# 2018.net
KiCad netlist of a schematic drawn in Altium Designer
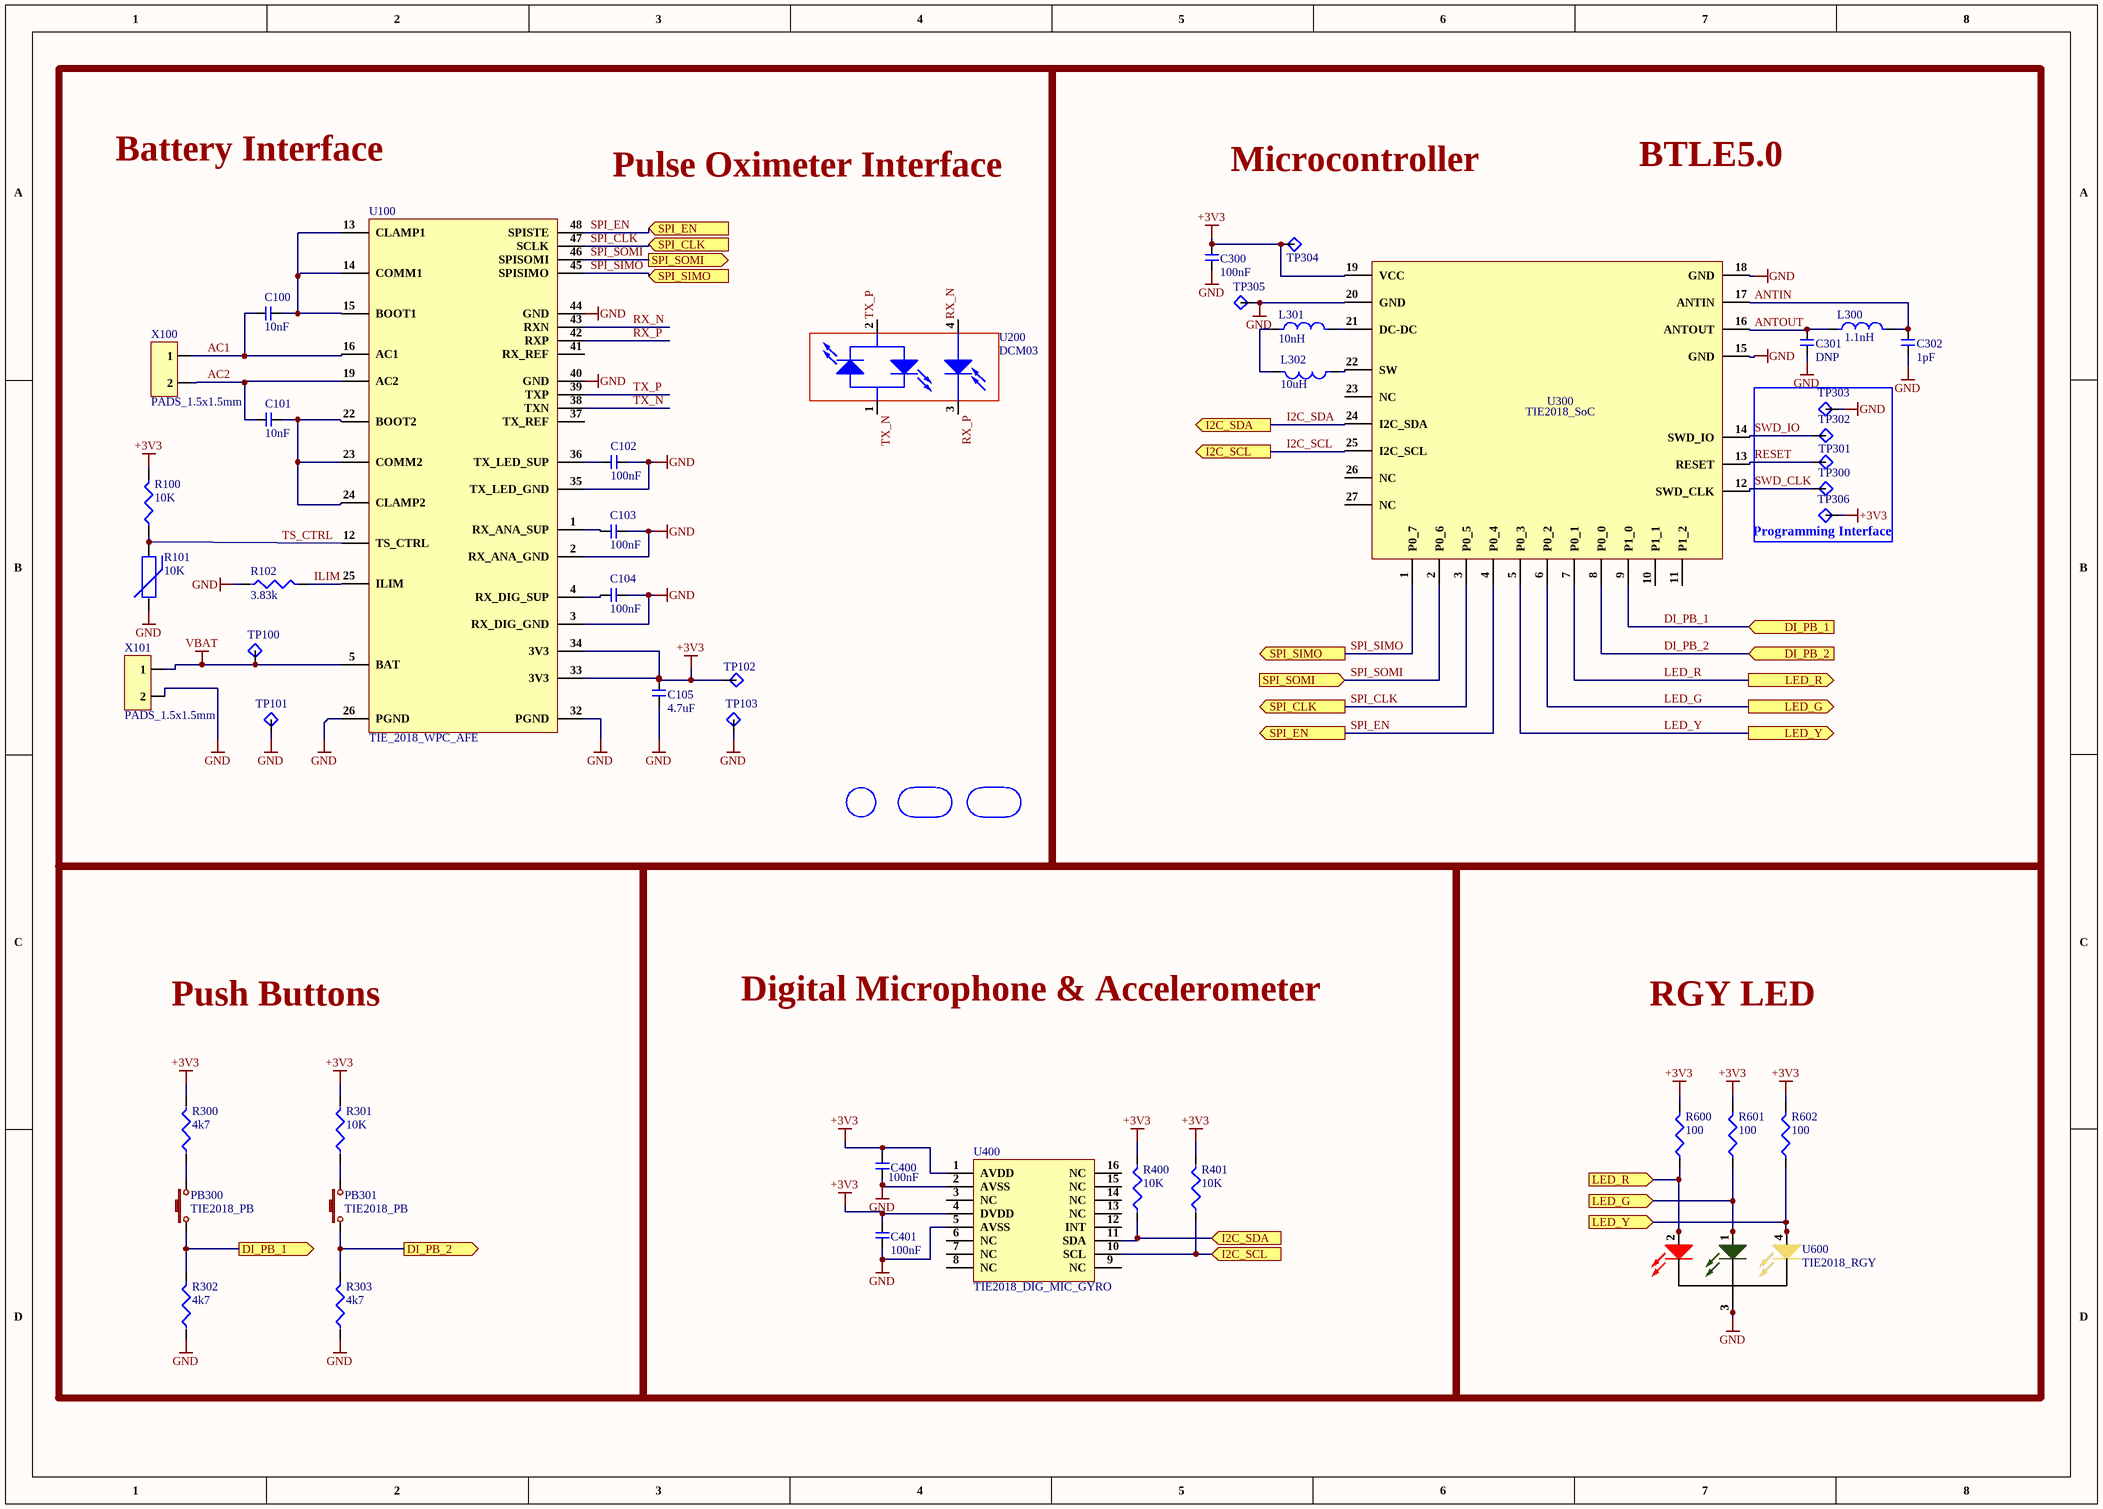
[diagram p0: 2018.SchDoc]

(export (version "E")
  (design (tool "Eeschema 10.0.6"))
  (components
    (comp (ref "C100")
      (value "10nF")
      (footprint "C0603")
      (description "Cap, 0.01ΜF, 25V, 1%, C0G/NP0, 0603")
      (fields
        (field (name "MANUFACTURER") "KEMET")
        (field (name "MANUFACTURER PART NUMBER") "C0603X103F3GACTU")
      )
      (libsource (lib "Gheorghe") (part "C0603X103F3GACTU"))
    )
    (comp (ref "C101")
      (value "10nF")
      (footprint "C0603")
      (description "Cap, 0.01ΜF, 25V, 1%, C0G/NP0, 0603")
      (fields
        (field (name "MANUFACTURER") "KEMET")
        (field (name "MANUFACTURER PART NUMBER") "C0603X103F3GACTU")
      )
      (libsource (lib "Gheorghe") (part "C0603X103F3GACTU"))
    )
    (comp (ref "C102")
      (value "100nF")
      (footprint "C0402")
      (description "Silicon Capacitor 100nF 11VDC 0402")
      (fields
        (field (name "MANUFACTURER") "Murata")
        (field (name "MANUFACTURER PART NUMBER") "939113424610-T3N")
      )
      (libsource (lib "Gheorghe") (part "939113424610-T3N"))
    )
    (comp (ref "C103")
      (value "100nF")
      (footprint "C0402")
      (description "Silicon Capacitor 100nF 11VDC 0402")
      (fields
        (field (name "MANUFACTURER") "Murata")
        (field (name "MANUFACTURER PART NUMBER") "939113424610-T3N")
      )
      (libsource (lib "Gheorghe") (part "939113424610-T3N"))
    )
    (comp (ref "C104")
      (value "100nF")
      (footprint "C0402")
      (description "Silicon Capacitor 100nF 11VDC 0402")
      (fields
        (field (name "MANUFACTURER") "Murata")
        (field (name "MANUFACTURER PART NUMBER") "939113424610-T3N")
      )
      (libsource (lib "Gheorghe") (part "939113424610-T3N"))
    )
    (comp (ref "C105")
      (value "4.7uF")
      (footprint "C0603")
      (description "C Series 0603 4.7 uF 35 V ±20 % Tolerance X5R SMT Multilayer Ceramic Capacitor")
      (fields
        (field (name "MANUFACTURER") "TDK")
        (field (name "MANUFACTURER PART NUMBER") "C1608X5R1V475M080AC")
      )
      (libsource (lib "Gheorghe") (part "C1608X5R1V475M080AC"))
    )
    (comp (ref "C300")
      (value "100nF")
      (footprint "C0402")
      (description "Silicon Capacitor 100nF 11VDC 0402")
      (fields
        (field (name "MANUFACTURER") "Murata")
        (field (name "MANUFACTURER PART NUMBER") "939113424610-T3N")
      )
      (libsource (lib "Gheorghe") (part "939113424610-T3N"))
    )
    (comp (ref "C301")
      (value "DNP")
      (footprint "C0402")
      (description "Cap Ceramic 100pF 10V X7R 20% SMD 0402 125°C Paper T/R")
      (fields
        (field (name "MANUFACTURER") "Kyocera AVX")
        (field (name "MANUFACTURER PART NUMBER") "0402ZC101MAT2A")
      )
      (libsource (lib "Gheorghe") (part "0402ZC101MAT2A"))
    )
    (comp (ref "C302")
      (value "1pF")
      (footprint "C0402")
      (description "Cap Ceramic 1pF 50V C0G 0.25pF Pad SMD 0402 125C Automotive T/R")
      (fields
        (field (name "MANUFACTURER") "Murata")
        (field (name "MANUFACTURER PART NUMBER") "GCM1555C1H1R0CA16J")
      )
      (libsource (lib "Gheorghe") (part "GCM1555C1H1R0CA16J"))
    )
    (comp (ref "C400")
      (value "100nF")
      (footprint "C0402")
      (description "Silicon Capacitor 100nF 11VDC 0402")
      (fields
        (field (name "MANUFACTURER") "Murata")
        (field (name "MANUFACTURER PART NUMBER") "939113424610-T3N")
      )
      (libsource (lib "Gheorghe") (part "939113424610-T3N"))
    )
    (comp (ref "C401")
      (value "100nF")
      (footprint "C0402")
      (description "Silicon Capacitor 100nF 11VDC 0402")
      (fields
        (field (name "MANUFACTURER") "Murata")
        (field (name "MANUFACTURER PART NUMBER") "939113424610-T3N")
      )
      (libsource (lib "Gheorghe") (part "939113424610-T3N"))
    )
    (comp (ref "L300")
      (value "1.1nH")
      (footprint "L0402")
      (fields
        (field (name "MANUFACTURER") "Murata")
        (field (name "MANUFACTURER PART NUMBER") "LQG15WZ1N1C02D")
      )
      (libsource (lib "Gheorghe") (part "LQG15WZ1N1C02D"))
    )
    (comp (ref "L301")
      (value "10nH")
      (footprint "L0402")
      (fields
        (field (name "MANUFACTURER") "TDK")
        (field (name "MANUFACTURER PART NUMBER") "MHQ1005P10NJT000")
        (field (name "TOLERANCE") "5%")
      )
      (libsource (lib "Gheorghe") (part "MHQ1005P10NJT000"))
    )
    (comp (ref "L302")
      (value "10uH")
      (footprint "L0603")
      (description "0603 10uH ±20% DCR=0.9Ω 50mA SRF=30MHz")
      (fields
        (field (name "MANUFACTURER") "Murata")
        (field (name "MANUFACTURER PART NUMBER") "LQM18FN100M00D")
      )
      (libsource (lib "Gheorghe") (part "LQM18FN100M00D"))
    )
    (comp (ref "MTH100")
      (value "MTH_2mmx2mm")
      (footprint "MTH_2mmx2mm")
      (libsource (lib "Gheorghe") (part "MTH_2mmx2mm"))
    )
    (comp (ref "MTH101")
      (value "MTH_2mmx3.5mm")
      (footprint "MTH_2mmx3.5mm")
      (libsource (lib "Gheorghe") (part "MTH_2mmx3.5mm"))
    )
    (comp (ref "MTH102")
      (value "MTH_2mmx3.5mm")
      (footprint "MTH_2mmx3.5mm")
      (libsource (lib "Gheorghe") (part "MTH_2mmx3.5mm"))
    )
    (comp (ref "PB300")
      (value "TIE2018_PB")
      (footprint "PB")
      (libsource (lib "Gheorghe") (part "Push_Button"))
    )
    (comp (ref "PB301")
      (value "TIE2018_PB")
      (footprint "PB")
      (libsource (lib "Gheorghe") (part "Push_Button"))
    )
    (comp (ref "R100")
      (value "10K")
      (footprint "R0402")
      (description "Res Thick Film 0402 10K Ohm 1% 1/16W ±100ppm/°C Molded SMD SMD Paper Tape on Plastic Reel")
      (fields
        (field (name "MANUFACTURER") "Bourns")
        (field (name "MANUFACTURER PART NUMBER") "CR0402-FX-1002GLF")
      )
      (libsource (lib "Gheorghe") (part "CR0402-FX-1002GLF"))
    )
    (comp (ref "R101")
      (value "10K")
      (footprint "R0402")
      (fields
        (field (name "MANUFACTURER") "Royal Electronic Factory")
        (field (name "MANUFACTURER PART NUMBER") "CQ02WGJ0103TCE")
      )
      (libsource (lib "Gheorghe") (part "CQ02WGJ0103TCE"))
    )
    (comp (ref "R102")
      (value "3.83k")
      (footprint "R0402")
      (description "Res Thick Film 0402 3.83K Ohm 1% 1/16W 100ppm/C Molded SMD SMD Paper Tape on Plastic Reel")
      (fields
        (field (name "MANUFACTURER") "Bourns")
        (field (name "MANUFACTURER PART NUMBER") "CR0402-FX-3831GLF")
      )
      (libsource (lib "Gheorghe") (part "CR0402-FX-3831GLF"))
    )
    (comp (ref "R300")
      (value "4k7")
      (footprint "R0402")
      (description "TNPU0402 4K7 0.1% T-16 EP1 E3")
      (fields
        (field (name "MANUFACTURER") "Vishay Dale")
        (field (name "MANUFACTURER PART NUMBER") "TNPU04024K70BZEP00")
      )
      (libsource (lib "Gheorghe") (part "TNPU04024K70BZEP00"))
    )
    (comp (ref "R301")
      (value "10K")
      (footprint "R0402")
      (description "Res Thick Film 0402 10K Ohm 1% 1/16W ±100ppm/°C Molded SMD SMD Paper Tape on Plastic Reel")
      (fields
        (field (name "MANUFACTURER") "Bourns")
        (field (name "MANUFACTURER PART NUMBER") "CR0402-FX-1002GLF")
      )
      (libsource (lib "Gheorghe") (part "CR0402-FX-1002GLF"))
    )
    (comp (ref "R302")
      (value "4k7")
      (footprint "R0402")
      (description "TNPU0402 4K7 0.1% T-16 EP1 E3")
      (fields
        (field (name "MANUFACTURER") "Vishay Dale")
        (field (name "MANUFACTURER PART NUMBER") "TNPU04024K70BZEP00")
      )
      (libsource (lib "Gheorghe") (part "TNPU04024K70BZEP00"))
    )
    (comp (ref "R303")
      (value "4k7")
      (footprint "R0402")
      (description "TNPU0402 4K7 0.1% T-16 EP1 E3")
      (fields
        (field (name "MANUFACTURER") "Vishay Dale")
        (field (name "MANUFACTURER PART NUMBER") "TNPU04024K70BZEP00")
      )
      (libsource (lib "Gheorghe") (part "TNPU04024K70BZEP00"))
    )
    (comp (ref "R400")
      (value "10K")
      (footprint "R0402")
      (description "Res Thick Film 0402 10K Ohm 1% 1/16W ±100ppm/°C Molded SMD SMD Paper Tape on Plastic Reel")
      (fields
        (field (name "MANUFACTURER") "Bourns")
        (field (name "MANUFACTURER PART NUMBER") "CR0402-FX-1002GLF")
      )
      (libsource (lib "Gheorghe") (part "CR0402-FX-1002GLF"))
    )
    (comp (ref "R401")
      (value "10K")
      (footprint "R0402")
      (description "Res Thick Film 0402 10K Ohm 1% 1/16W ±100ppm/°C Molded SMD SMD Paper Tape on Plastic Reel")
      (fields
        (field (name "MANUFACTURER") "Bourns")
        (field (name "MANUFACTURER PART NUMBER") "CR0402-FX-1002GLF")
      )
      (libsource (lib "Gheorghe") (part "CR0402-FX-1002GLF"))
    )
    (comp (ref "R600")
      (value "100")
      (footprint "R0402")
      (description "Res Thick Film 0402 100 Ohm 1% 1/16W ±100ppm/°C Molded SMD SMD Paper Tape on Plastic Reel")
      (fields
        (field (name "MANUFACTURER") "Bourns")
        (field (name "MANUFACTURER PART NUMBER") "CR0402-FX-1000GLF")
      )
      (libsource (lib "Gheorghe") (part "CR0402-FX-1000GLF"))
    )
    (comp (ref "R601")
      (value "100")
      (footprint "R0402")
      (description "Res Thick Film 0402 100 Ohm 1% 1/16W ±100ppm/°C Molded SMD SMD Paper Tape on Plastic Reel")
      (fields
        (field (name "MANUFACTURER") "Bourns")
        (field (name "MANUFACTURER PART NUMBER") "CR0402-FX-1000GLF")
      )
      (libsource (lib "Gheorghe") (part "CR0402-FX-1000GLF"))
    )
    (comp (ref "R602")
      (value "100")
      (footprint "R0402")
      (description "Res Thick Film 0402 100 Ohm 1% 1/16W ±100ppm/°C Molded SMD SMD Paper Tape on Plastic Reel")
      (fields
        (field (name "MANUFACTURER") "Bourns")
        (field (name "MANUFACTURER PART NUMBER") "CR0402-FX-1000GLF")
      )
      (libsource (lib "Gheorghe") (part "CR0402-FX-1000GLF"))
    )
    (comp (ref "TP100")
      (value "Test_Point_3")
      (footprint "TestPoint")
      (libsource (lib "Gheorghe") (part "Test_Point_3"))
    )
    (comp (ref "TP101")
      (value "Test_Point_3")
      (footprint "TestPoint")
      (libsource (lib "Gheorghe") (part "Test_Point_3"))
    )
    (comp (ref "TP102")
      (value "Test_Point_3")
      (footprint "TestPoint")
      (libsource (lib "Gheorghe") (part "Test_Point_3"))
    )
    (comp (ref "TP103")
      (value "Test_Point_3")
      (footprint "TestPoint")
      (libsource (lib "Gheorghe") (part "Test_Point_3"))
    )
    (comp (ref "TP300")
      (value "Test_Point_3")
      (footprint "TestPoint")
      (libsource (lib "Gheorghe") (part "Test_Point_3"))
    )
    (comp (ref "TP301")
      (value "Test_Point_3")
      (footprint "TestPoint")
      (libsource (lib "Gheorghe") (part "Test_Point_3"))
    )
    (comp (ref "TP302")
      (value "Test_Point_3")
      (footprint "TestPoint")
      (libsource (lib "Gheorghe") (part "Test_Point_3"))
    )
    (comp (ref "TP303")
      (value "Test_Point_3")
      (footprint "TestPoint")
      (libsource (lib "Gheorghe") (part "Test_Point_3"))
    )
    (comp (ref "TP304")
      (value "Test_Point_3")
      (footprint "TestPoint")
      (libsource (lib "Gheorghe") (part "Test_Point_3"))
    )
    (comp (ref "TP305")
      (value "Test_Point_3")
      (footprint "TestPoint")
      (libsource (lib "Gheorghe") (part "Test_Point_3"))
    )
    (comp (ref "TP306")
      (value "Test_Point_3")
      (footprint "TestPoint")
      (libsource (lib "Gheorghe") (part "Test_Point_3"))
    )
    (comp (ref "U100")
      (value "TIE_2018_WPC_AFE")
      (footprint "WPC_AFE")
      (libsource (lib "Gheorghe") (part "WPC_AFE"))
    )
    (comp (ref "U200") (value "DCM03") (footprint "DMC03") (libsource (lib "Gheorghe") (part "DCM03")))
    (comp (ref "U300") (value "TIE2018_SoC") (footprint "SoC") (libsource (lib "Gheorghe") (part "SoC")))
    (comp (ref "U400")
      (value "TIE2018_DIG_MIC_GYRO")
      (footprint "DIGI_MIC_GYRO")
      (libsource (lib "Gheorghe") (part "DIG_MIC_GYRO"))
    )
    (comp (ref "U600")
      (value "TIE2018_RGY")
      (footprint "SMP4-RGY")
      (description "LED SMD PLCC4 Tri-Color Red/Green/Yellow Clr Lens 120Deg View Angle")
      (fields (field (name "MANUFACTURER") "Bivar") (field (name "MANUFACTURER PART NUMBER") "SMP4-RGY"))
      (libsource (lib "Gheorghe") (part "SMP4-RGY"))
    )
    (comp (ref "X100")
      (value "PADS_1.5x1.5mm")
      (footprint "PADS_1.5x1.5mm")
      (libsource (lib "Gheorghe") (part "PADS_1.5x1.5mm"))
    )
    (comp (ref "X101")
      (value "PADS_1.5x1.5mm")
      (footprint "PADS_1.5x1.5mm")
      (libsource (lib "Gheorghe") (part "PADS_1.5x1.5mm"))
    )
  )
  (nets
    (net (code "1") (name "+3V3") (class "Default")
      (node (ref "C105") (pin "2") (pinfunction "2_2") (pintype "passive"))
      (node (ref "C300") (pin "2") (pinfunction "2_2") (pintype "passive"))
      (node (ref "C400") (pin "2") (pinfunction "2_2") (pintype "passive"))
      (node (ref "C401") (pin "2") (pinfunction "2_2") (pintype "passive"))
      (node (ref "R100") (pin "2") (pinfunction "2_2") (pintype "passive"))
      (node (ref "R300") (pin "2") (pinfunction "2_2") (pintype "passive"))
      (node (ref "R301") (pin "2") (pinfunction "2_2") (pintype "passive"))
      (node (ref "R400") (pin "2") (pinfunction "2_2") (pintype "passive"))
      (node (ref "R401") (pin "2") (pinfunction "2_2") (pintype "passive"))
      (node (ref "R600") (pin "2") (pinfunction "2_2") (pintype "passive"))
      (node (ref "R601") (pin "2") (pinfunction "2_2") (pintype "passive"))
      (node (ref "R602") (pin "2") (pinfunction "2_2") (pintype "passive"))
      (node (ref "TP102") (pin "1") (pinfunction "1_1") (pintype "passive"))
      (node (ref "TP304") (pin "1") (pinfunction "1_1") (pintype "passive"))
      (node (ref "TP306") (pin "1") (pinfunction "1_1") (pintype "passive"))
      (node (ref "U100") (pin "33") (pinfunction "3V3_33") (pintype "passive"))
      (node (ref "U100") (pin "34") (pinfunction "3V3_34") (pintype "passive"))
      (node (ref "U300") (pin "19") (pinfunction "VCC_19") (pintype "passive"))
      (node (ref "U400") (pin "1") (pinfunction "AVDD_1") (pintype "passive"))
      (node (ref "U400") (pin "4") (pinfunction "DVDD_4") (pintype "passive"))
    )
    (net (code "2") (name "/AC1") (class "Default")
      (node (ref "C100") (pin "1") (pinfunction "1_1") (pintype "passive"))
      (node (ref "U100") (pin "16") (pinfunction "AC1_16") (pintype "passive"))
      (node (ref "X100") (pin "1") (pinfunction "1_1") (pintype "passive"))
    )
    (net (code "3") (name "/AC2") (class "Default")
      (node (ref "C101") (pin "1") (pinfunction "1_1") (pintype "passive"))
      (node (ref "U100") (pin "19") (pinfunction "AC2_19") (pintype "passive"))
      (node (ref "X100") (pin "2") (pinfunction "2_2") (pintype "passive"))
    )
    (net (code "4") (name "/ANTIN") (class "Default")
      (node (ref "C302") (pin "2") (pinfunction "2_2") (pintype "passive"))
      (node (ref "L300") (pin "2") (pinfunction "2_2") (pintype "passive"))
      (node (ref "U300") (pin "17") (pinfunction "ANTIN_17") (pintype "passive"))
    )
    (net (code "5") (name "/ANTOUT") (class "Default")
      (node (ref "C301") (pin "2") (pinfunction "2_2") (pintype "passive"))
      (node (ref "L300") (pin "1") (pinfunction "1_1") (pintype "passive"))
      (node (ref "U300") (pin "16") (pinfunction "ANTOUT_16") (pintype "passive"))
    )
    (net (code "6") (name "/DI_PB_1") (class "Default")
      (node (ref "PB300") (pin "1") (pinfunction "1_1") (pintype "passive"))
      (node (ref "R302") (pin "2") (pinfunction "2_2") (pintype "passive"))
      (node (ref "U300") (pin "9") (pinfunction "P1_0_9") (pintype "passive"))
    )
    (net (code "7") (name "/DI_PB_2") (class "Default")
      (node (ref "PB301") (pin "1") (pinfunction "1_1") (pintype "passive"))
      (node (ref "R303") (pin "2") (pinfunction "2_2") (pintype "passive"))
      (node (ref "U300") (pin "8") (pinfunction "P0_0_8") (pintype "passive"))
    )
    (net (code "8") (name "/I2C_SCL") (class "Default")
      (node (ref "R401") (pin "1") (pinfunction "1_1") (pintype "passive"))
      (node (ref "U300") (pin "25") (pinfunction "I2C_SCL_25") (pintype "passive"))
      (node (ref "U400") (pin "10") (pinfunction "SCL_10") (pintype "passive"))
    )
    (net (code "9") (name "/I2C_SDA") (class "Default")
      (node (ref "R400") (pin "1") (pinfunction "1_1") (pintype "passive"))
      (node (ref "U300") (pin "24") (pinfunction "I2C_SDA_24") (pintype "passive"))
      (node (ref "U400") (pin "11") (pinfunction "SDA_11") (pintype "passive"))
    )
    (net (code "10") (name "/ILIM") (class "Default")
      (node (ref "R102") (pin "2") (pinfunction "2_2") (pintype "passive"))
      (node (ref "U100") (pin "25") (pinfunction "ILIM_25") (pintype "passive"))
    )
    (net (code "11") (name "/LED_G") (class "Default")
      (node (ref "R601") (pin "1") (pinfunction "1_1") (pintype "passive"))
      (node (ref "U300") (pin "6") (pinfunction "P0_2_6") (pintype "passive"))
      (node (ref "U600") (pin "1") (pinfunction "1_1") (pintype "passive"))
    )
    (net (code "12") (name "/LED_R") (class "Default")
      (node (ref "R600") (pin "1") (pinfunction "1_1") (pintype "passive"))
      (node (ref "U300") (pin "7") (pinfunction "P0_1_7") (pintype "passive"))
      (node (ref "U600") (pin "2") (pinfunction "2_2") (pintype "passive"))
    )
    (net (code "13") (name "/LED_Y") (class "Default")
      (node (ref "R602") (pin "1") (pinfunction "1_1") (pintype "passive"))
      (node (ref "U300") (pin "5") (pinfunction "P0_3_5") (pintype "passive"))
      (node (ref "U600") (pin "4") (pinfunction "4_4") (pintype "passive"))
    )
    (net (code "14") (name "/RESET") (class "Default")
      (node (ref "TP301") (pin "1") (pinfunction "1_1") (pintype "passive"))
      (node (ref "U300") (pin "13") (pinfunction "RESET_13") (pintype "passive"))
    )
    (net (code "15") (name "/RX_N") (class "Default")
      (node (ref "U100") (pin "43") (pinfunction "RXN_43") (pintype "passive"))
      (node (ref "U200") (pin "4") (pinfunction "4_4") (pintype "passive"))
    )
    (net (code "16") (name "/RX_P") (class "Default")
      (node (ref "U100") (pin "42") (pinfunction "RXP_42") (pintype "passive"))
      (node (ref "U200") (pin "3") (pinfunction "3_3") (pintype "passive"))
    )
    (net (code "17") (name "/SPI_CLK") (class "Default")
      (node (ref "U100") (pin "47") (pinfunction "SCLK_47") (pintype "passive"))
      (node (ref "U300") (pin "3") (pinfunction "P0_5_3") (pintype "passive"))
    )
    (net (code "18") (name "/SPI_EN") (class "Default")
      (node (ref "U100") (pin "48") (pinfunction "SPISTE_48") (pintype "passive"))
      (node (ref "U300") (pin "4") (pinfunction "P0_4_4") (pintype "passive"))
    )
    (net (code "19") (name "/SPI_SIMO") (class "Default")
      (node (ref "U100") (pin "45") (pinfunction "SPISIMO_45") (pintype "passive"))
      (node (ref "U300") (pin "1") (pinfunction "P0_7_1") (pintype "passive"))
    )
    (net (code "20") (name "/SPI_SOMI") (class "Default")
      (node (ref "U100") (pin "46") (pinfunction "SPISOMI_46") (pintype "passive"))
      (node (ref "U300") (pin "2") (pinfunction "P0_6_2") (pintype "passive"))
    )
    (net (code "21") (name "/SWD_CLK") (class "Default")
      (node (ref "TP300") (pin "1") (pinfunction "1_1") (pintype "passive"))
      (node (ref "U300") (pin "12") (pinfunction "SWD_CLK_12") (pintype "passive"))
    )
    (net (code "22") (name "/SWD_IO") (class "Default")
      (node (ref "TP302") (pin "1") (pinfunction "1_1") (pintype "passive"))
      (node (ref "U300") (pin "14") (pinfunction "SWD_IO_14") (pintype "passive"))
    )
    (net (code "24") (name "/TS_CTRL") (class "Default")
      (node (ref "R100") (pin "1") (pinfunction "1_1") (pintype "passive"))
      (node (ref "R101") (pin "2") (pinfunction "2_2") (pintype "passive"))
      (node (ref "U100") (pin "12") (pinfunction "TS_CTRL_12") (pintype "passive"))
    )
    (net (code "25") (name "/TX_N") (class "Default")
      (node (ref "U100") (pin "38") (pinfunction "TXN_38") (pintype "passive"))
      (node (ref "U200") (pin "1") (pinfunction "1_1") (pintype "passive"))
    )
    (net (code "26") (name "/TX_P") (class "Default")
      (node (ref "U100") (pin "39") (pinfunction "TXP_39") (pintype "passive"))
      (node (ref "U200") (pin "2") (pinfunction "2_2") (pintype "passive"))
    )
    (net (code "27") (name "GND") (class "Default")
      (node (ref "C102") (pin "2") (pinfunction "2_2") (pintype "passive"))
      (node (ref "C103") (pin "2") (pinfunction "2_2") (pintype "passive"))
      (node (ref "C104") (pin "2") (pinfunction "2_2") (pintype "passive"))
      (node (ref "C105") (pin "1") (pinfunction "1_1") (pintype "passive"))
      (node (ref "C300") (pin "1") (pinfunction "1_1") (pintype "passive"))
      (node (ref "C301") (pin "1") (pinfunction "1_1") (pintype "passive"))
      (node (ref "C302") (pin "1") (pinfunction "1_1") (pintype "passive"))
      (node (ref "C400") (pin "1") (pinfunction "1_1") (pintype "passive"))
      (node (ref "C401") (pin "1") (pinfunction "1_1") (pintype "passive"))
      (node (ref "R101") (pin "1") (pinfunction "1_1") (pintype "passive"))
      (node (ref "R102") (pin "1") (pinfunction "1_1") (pintype "passive"))
      (node (ref "R302") (pin "1") (pinfunction "1_1") (pintype "passive"))
      (node (ref "R303") (pin "1") (pinfunction "1_1") (pintype "passive"))
      (node (ref "TP101") (pin "1") (pinfunction "1_1") (pintype "passive"))
      (node (ref "TP103") (pin "1") (pinfunction "1_1") (pintype "passive"))
      (node (ref "TP303") (pin "1") (pinfunction "1_1") (pintype "passive"))
      (node (ref "TP305") (pin "1") (pinfunction "1_1") (pintype "passive"))
      (node (ref "U100") (pin "2") (pinfunction "RX_ANA_GND_2") (pintype "passive"))
      (node (ref "U100") (pin "26") (pinfunction "PGND_26") (pintype "passive"))
      (node (ref "U100") (pin "3") (pinfunction "RX_DIG_GND_3") (pintype "passive"))
      (node (ref "U100") (pin "32") (pinfunction "PGND_32") (pintype "passive"))
      (node (ref "U100") (pin "35") (pinfunction "TX_LED_GND_35") (pintype "passive"))
      (node (ref "U100") (pin "40") (pinfunction "GND_40") (pintype "passive"))
      (node (ref "U100") (pin "44") (pinfunction "GND_44") (pintype "passive"))
      (node (ref "U300") (pin "15") (pinfunction "GND_15") (pintype "passive"))
      (node (ref "U300") (pin "18") (pinfunction "GND_18") (pintype "passive"))
      (node (ref "U300") (pin "20") (pinfunction "GND_20") (pintype "passive"))
      (node (ref "U400") (pin "2") (pinfunction "AVSS_2") (pintype "passive"))
      (node (ref "U400") (pin "5") (pinfunction "AVSS_5") (pintype "passive"))
      (node (ref "U600") (pin "3") (pinfunction "3_3") (pintype "passive"))
      (node (ref "X101") (pin "2") (pinfunction "2_2") (pintype "passive"))
    )
    (net (code "28") (name "Net-(L301-Pad1)") (class "Default")
      (node (ref "L301") (pin "1") (pinfunction "1_1") (pintype "passive"))
      (node (ref "L302") (pin "1") (pinfunction "1_1") (pintype "passive"))
    )
    (net (code "29") (name "Net-(PB300-Pad2)") (class "Default")
      (node (ref "PB300") (pin "2") (pinfunction "2_2") (pintype "passive"))
      (node (ref "R300") (pin "1") (pinfunction "1_1") (pintype "passive"))
    )
    (net (code "30") (name "Net-(PB301-Pad2)") (class "Default")
      (node (ref "PB301") (pin "2") (pinfunction "2_2") (pintype "passive"))
      (node (ref "R301") (pin "1") (pinfunction "1_1") (pintype "passive"))
    )
    (net (code "31") (name "Net-(U100-BOOT1)") (class "Default")
      (node (ref "C100") (pin "2") (pinfunction "2_2") (pintype "passive"))
      (node (ref "U100") (pin "13") (pinfunction "CLAMP1_13") (pintype "passive"))
      (node (ref "U100") (pin "14") (pinfunction "COMM1_14") (pintype "passive"))
      (node (ref "U100") (pin "15") (pinfunction "BOOT1_15") (pintype "passive"))
    )
    (net (code "32") (name "Net-(U100-BOOT2)") (class "Default")
      (node (ref "C101") (pin "2") (pinfunction "2_2") (pintype "passive"))
      (node (ref "U100") (pin "22") (pinfunction "BOOT2_22") (pintype "passive"))
      (node (ref "U100") (pin "23") (pinfunction "COMM2_23") (pintype "passive"))
      (node (ref "U100") (pin "24") (pinfunction "CLAMP2_24") (pintype "passive"))
    )
    (net (code "33") (name "Net-(U100-RX_ANA_SUP)") (class "Default")
      (node (ref "C103") (pin "1") (pinfunction "1_1") (pintype "passive"))
      (node (ref "U100") (pin "1") (pinfunction "RX_ANA_SUP_1") (pintype "passive"))
    )
    (net (code "34") (name "Net-(U100-RX_DIG_SUP)") (class "Default")
      (node (ref "C104") (pin "1") (pinfunction "1_1") (pintype "passive"))
      (node (ref "U100") (pin "4") (pinfunction "RX_DIG_SUP_4") (pintype "passive"))
    )
    (net (code "35") (name "Net-(U100-TX_LED_SUP)") (class "Default")
      (node (ref "C102") (pin "1") (pinfunction "1_1") (pintype "passive"))
      (node (ref "U100") (pin "36") (pinfunction "TX_LED_SUP_36") (pintype "passive"))
    )
    (net (code "36") (name "Net-(U300-DC-DC)") (class "Default")
      (node (ref "L301") (pin "2") (pinfunction "2_2") (pintype "passive"))
      (node (ref "U300") (pin "21") (pinfunction "DC-DC_21") (pintype "passive"))
    )
    (net (code "37") (name "Net-(U300-SW)") (class "Default")
      (node (ref "L302") (pin "2") (pinfunction "2_2") (pintype "passive"))
      (node (ref "U300") (pin "22") (pinfunction "SW_22") (pintype "passive"))
    )
    (net (code "38") (name "VBAT") (class "Default")
      (node (ref "TP100") (pin "1") (pinfunction "1_1") (pintype "passive"))
      (node (ref "U100") (pin "5") (pinfunction "BAT_5") (pintype "passive"))
      (node (ref "X101") (pin "1") (pinfunction "1_1") (pintype "passive"))
    )
    (net (code "39") (name "unconnected-(U100-RX_REF-Pad41)") (class "Default")
      (node (ref "U100") (pin "41") (pinfunction "RX_REF_41") (pintype "passive"))
    )
    (net (code "40") (name "unconnected-(U100-TX_REF-Pad37)") (class "Default")
      (node (ref "U100") (pin "37") (pinfunction "TX_REF_37") (pintype "passive"))
    )
    (net (code "41") (name "unconnected-(U300-NC-Pad23)") (class "Default")
      (node (ref "U300") (pin "23") (pinfunction "NC_23") (pintype "passive"))
    )
    (net (code "42") (name "unconnected-(U300-NC-Pad26)") (class "Default")
      (node (ref "U300") (pin "26") (pinfunction "NC_26") (pintype "passive"))
    )
    (net (code "43") (name "unconnected-(U300-NC-Pad27)") (class "Default")
      (node (ref "U300") (pin "27") (pinfunction "NC_27") (pintype "passive"))
    )
    (net (code "44") (name "unconnected-(U300-P1_1-Pad10)") (class "Default")
      (node (ref "U300") (pin "10") (pinfunction "P1_1_10") (pintype "passive"))
    )
    (net (code "45") (name "unconnected-(U300-P1_2-Pad11)") (class "Default")
      (node (ref "U300") (pin "11") (pinfunction "P1_2_11") (pintype "passive"))
    )
    (net (code "46") (name "unconnected-(U400-INT-Pad12)") (class "Default")
      (node (ref "U400") (pin "12") (pinfunction "INT_12") (pintype "passive"))
    )
    (net (code "47") (name "unconnected-(U400-NC-Pad3)") (class "Default")
      (node (ref "U400") (pin "3") (pinfunction "NC_3") (pintype "passive"))
    )
    (net (code "48") (name "unconnected-(U400-NC-Pad6)") (class "Default")
      (node (ref "U400") (pin "6") (pinfunction "NC_6") (pintype "passive"))
    )
    (net (code "49") (name "unconnected-(U400-NC-Pad7)") (class "Default")
      (node (ref "U400") (pin "7") (pinfunction "NC_7") (pintype "passive"))
    )
    (net (code "50") (name "unconnected-(U400-NC-Pad8)") (class "Default")
      (node (ref "U400") (pin "8") (pinfunction "NC_8") (pintype "passive"))
    )
    (net (code "51") (name "unconnected-(U400-NC-Pad9)") (class "Default")
      (node (ref "U400") (pin "9") (pinfunction "NC_9") (pintype "passive"))
    )
    (net (code "52") (name "unconnected-(U400-NC-Pad13)") (class "Default")
      (node (ref "U400") (pin "13") (pinfunction "NC_13") (pintype "passive"))
    )
    (net (code "53") (name "unconnected-(U400-NC-Pad14)") (class "Default")
      (node (ref "U400") (pin "14") (pinfunction "NC_14") (pintype "passive"))
    )
    (net (code "54") (name "unconnected-(U400-NC-Pad15)") (class "Default")
      (node (ref "U400") (pin "15") (pinfunction "NC_15") (pintype "passive"))
    )
    (net (code "55") (name "unconnected-(U400-NC-Pad16)") (class "Default")
      (node (ref "U400") (pin "16") (pinfunction "NC_16") (pintype "passive"))
    )
  )
)
